# Rs485_Interface.net
KiCad netlist of a schematic drawn in Altium Designer
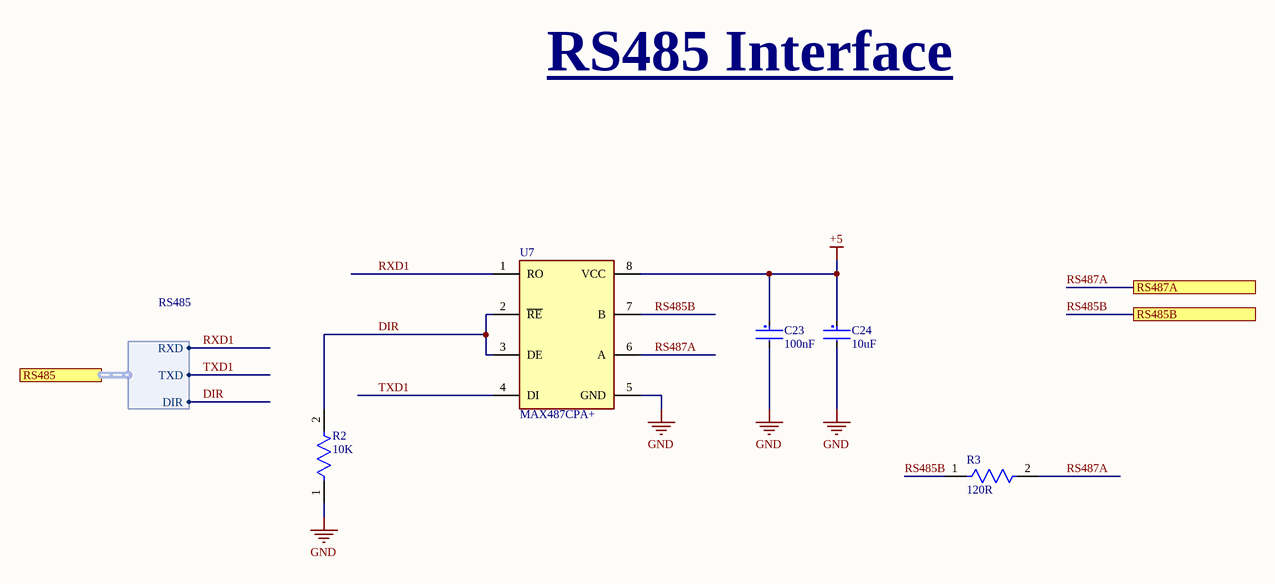
[diagram p0: Rs485_Interface.SchDoc]

(export (version "E")
  (design (tool "Eeschema 10.0.6"))
  (components
    (comp (ref "C23")
      (value "100nF")
      (footprint "Samsung_CL31_IPC_A_1206")
      (description "CAP CER 0.1UF 50V X7R 1206, ±10% 50V Ceramic Capacitor X7R 1206 (3216 Metric)")
      (libsource (lib "DMD_Card") (part "CL31B104KBCNFNC"))
    )
    (comp (ref "C24")
      (value "10uF")
      (footprint "Samsung_CL31_IPC_A_1206")
      (description "CAP CER 10UF 6.3V X5R 1206, ±10% 6.3V Ceramic Capacitor X5R 1206 (3216 Metric)")
      (libsource (lib "DMD_Card") (part "CL31A106KQHNNWE"))
    )
    (comp (ref "R2")
      (value "10K")
      (footprint "YAGEO_RC1206-0_65_IPC_A")
      (description "10 ±1% 0.25W, 1/4W Chip Resistor 1206 (3216 Metric) Moisture Resistant Thick Film")
      (libsource (lib "DMD_Card") (part "RC1206FR-0710KL"))
    )
    (comp (ref "R3")
      (value "120R")
      (footprint "AXIAL 0.4")
      (description "RES 120 OHM 1/4W 0.1% AXIAL")
      (fields
        (field (name "MANUFACTURER") "Yageo")
        (field (name "MANUFACTURER PART NUMBER") "MFP-25BRD52-120R")
      )
      (libsource (lib "DMD_Card") (part "120R 1/4W"))
    )
    (comp (ref "U7")
      (value "MAX487CPA+")
      (footprint "SOIC-8")
      (description "Interface IC RS422/485 DIL-8, MAX487ECPA+, Maxim")
      (fields (field (name "MANUFACTURER") "Maxim") (field (name "MANUFACTURER PART NUMBER") "MAX487ECPA+"))
      (libsource (lib "DMD_Card") (part "MAX487ECPA+"))
    )
  )
  (nets
    (net (code "2") (name "+5") (class "Default")
      (node (ref "C23") (pin "1") (pinfunction "1_1") (pintype "passive"))
      (node (ref "C24") (pin "1") (pinfunction "1_1") (pintype "passive"))
      (node (ref "U7") (pin "8") (pinfunction "VCC_8") (pintype "passive"))
    )
    (net (code "3") (name "/DIR") (class "Default")
      (node (ref "R2") (pin "2") (pinfunction "2_2") (pintype "passive"))
      (node (ref "U7") (pin "2") (pinfunction "~{RE}_2") (pintype "passive"))
      (node (ref "U7") (pin "3") (pinfunction "DE_3") (pintype "passive"))
    )
    (net (code "4") (name "/RS485B") (class "Default")
      (node (ref "R3") (pin "1") (pinfunction "1_1") (pintype "passive"))
      (node (ref "U7") (pin "7") (pinfunction "B_7") (pintype "passive"))
    )
    (net (code "5") (name "/RS487A") (class "Default")
      (node (ref "R3") (pin "2") (pinfunction "2_2") (pintype "passive"))
      (node (ref "U7") (pin "6") (pinfunction "A_6") (pintype "passive"))
    )
    (net (code "6") (name "/RXD1") (class "Default")
      (node (ref "U7") (pin "1") (pinfunction "RO_1") (pintype "passive"))
    )
    (net (code "7") (name "/TXD1") (class "Default")
      (node (ref "U7") (pin "4") (pinfunction "DI_4") (pintype "passive"))
    )
    (net (code "9") (name "GND") (class "Default")
      (node (ref "C23") (pin "2") (pinfunction "2_2") (pintype "passive"))
      (node (ref "C24") (pin "2") (pinfunction "2_2") (pintype "passive"))
      (node (ref "R2") (pin "1") (pinfunction "1_1") (pintype "passive"))
      (node (ref "U7") (pin "5") (pinfunction "GND_5") (pintype "passive"))
    )
  )
)
